# Multivibrator.net
KiCad netlist of a schematic drawn in Altium Designer
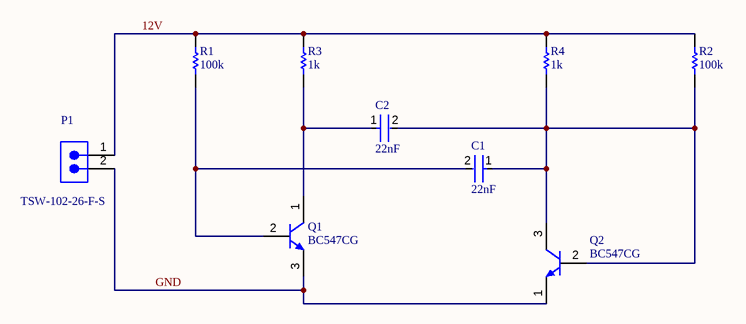
[diagram p0: Multivibrator.SchDoc]

(export (version "E")
  (design (tool "Eeschema 10.0.6"))
  (components
    (comp (ref "C1")
      (value "22nF")
      (footprint "FP-C0603C-CF-IPC_A")
      (fields (field (name "Comment") "Capacitor 22nF +/-5% 16V 0603"))
      (libsource (lib "Georges Lab") (part "b4654b650e69147ec39a6b967a45e02"))
    )
    (comp (ref "C2")
      (value "22nF")
      (footprint "FP-C0603C-CF-IPC_A")
      (fields (field (name "Comment") "Capacitor 22nF +/-5% 16V 0603"))
      (libsource (lib "Georges Lab") (part "b4654b650e69147ec39a6b967a45e02"))
    )
    (comp (ref "P1")
      (value "TSW-102-26-F-S")
      (footprint "SMTC-TSW-102-26-XX-S")
      (libsource (lib "Georges Lab") (part "SMTC-TSW-102-X-X-S-X"))
    )
    (comp (ref "Q1")
      (value "BC547CG")
      (footprint "ONSC-TO-92-3-29-11")
      (description "Small Signal Bipolar Transistor, 0.1A I(C), 45V V(BR)CEO, 1-Element, NPN, Silicon, TO-92")
      (libsource (lib "") (part "ONSC-NPN-C1B2E3-3_1"))
    )
    (comp (ref "Q2")
      (value "BC547CG")
      (footprint "ONSC-TO-92-3-29-11")
      (description "Small Signal Bipolar Transistor, 0.1A I(C), 45V V(BR)CEO, 1-Element, NPN, Silicon, TO-92")
      (libsource (lib "Georges Lab") (part "ONSC-NPN-C1B2E3-3"))
    )
    (comp (ref "R1")
      (value "100k")
      (footprint "RESC2013X70X40ML20T20")
      (fields
        (field (name "TOLERANCE") "5%")
        (field (name "POWER") "125mW")
        (field (name "Comment") "Resistor 100K +/-5% 0805 125 mW")
      )
      (libsource (lib "Georges Lab") (part "RES"))
    )
    (comp (ref "R2")
      (value "100k")
      (footprint "RESC2013X70X40ML20T20")
      (fields
        (field (name "TOLERANCE") "5%")
        (field (name "POWER") "125mW")
        (field (name "Comment") "Resistor 100K +/-5% 0805 125 mW")
      )
      (libsource (lib "Georges Lab") (part "RES"))
    )
    (comp (ref "R3")
      (value "1k")
      (footprint "RESC2013X70X40ML20T20")
      (fields
        (field (name "POWER") "125mW")
        (field (name "TOLERANCE") "5%")
        (field (name "Comment") "Resistor 1K +/-5% 0805 500 mW")
      )
      (libsource (lib "Georges Lab") (part "RES"))
    )
    (comp (ref "R4")
      (value "1k")
      (footprint "RESC2013X70X40ML20T20")
      (fields
        (field (name "POWER") "125mW")
        (field (name "TOLERANCE") "5%")
        (field (name "Comment") "Resistor 1K +/-5% 0805 500 mW")
      )
      (libsource (lib "Georges Lab") (part "RES"))
    )
  )
  (nets
    (net (code "1") (name "/12V") (class "Default")
      (node (ref "P1") (pin "1") (pinfunction "1_1") (pintype "passive"))
      (node (ref "R1") (pin "2") (pinfunction "2_2") (pintype "passive"))
      (node (ref "R2") (pin "2") (pinfunction "2_2") (pintype "passive"))
      (node (ref "R3") (pin "2") (pinfunction "2_2") (pintype "passive"))
      (node (ref "R4") (pin "2") (pinfunction "2_2") (pintype "passive"))
    )
    (net (code "2") (name "/GND") (class "Default")
      (node (ref "P1") (pin "2") (pinfunction "2_2") (pintype "passive"))
      (node (ref "Q1") (pin "3") (pinfunction "E_3") (pintype "passive"))
      (node (ref "Q2") (pin "1") (pinfunction "C_1") (pintype "passive"))
    )
    (net (code "3") (name "Net-(Q1-B)") (class "Default")
      (node (ref "C1") (pin "2") (pinfunction "2_2") (pintype "passive"))
      (node (ref "Q1") (pin "2") (pinfunction "B_2") (pintype "passive"))
      (node (ref "R1") (pin "1") (pinfunction "1_1") (pintype "passive"))
    )
    (net (code "4") (name "Net-(Q1-C)") (class "Default")
      (node (ref "C2") (pin "1") (pinfunction "1_1") (pintype "passive"))
      (node (ref "Q1") (pin "1") (pinfunction "C_1") (pintype "passive"))
      (node (ref "R3") (pin "1") (pinfunction "1_1") (pintype "passive"))
    )
    (net (code "5") (name "Net-(Q2-B)") (class "Default")
      (node (ref "C1") (pin "1") (pinfunction "1_1") (pintype "passive"))
      (node (ref "C2") (pin "2") (pinfunction "2_2") (pintype "passive"))
      (node (ref "Q2") (pin "2") (pinfunction "B_2") (pintype "passive"))
      (node (ref "Q2") (pin "3") (pinfunction "E_3") (pintype "passive"))
      (node (ref "R2") (pin "1") (pinfunction "1_1") (pintype "passive"))
      (node (ref "R4") (pin "1") (pinfunction "1_1") (pintype "passive"))
    )
  )
)
